# stimulation.net
KiCad netlist of a schematic drawn in EAGLE
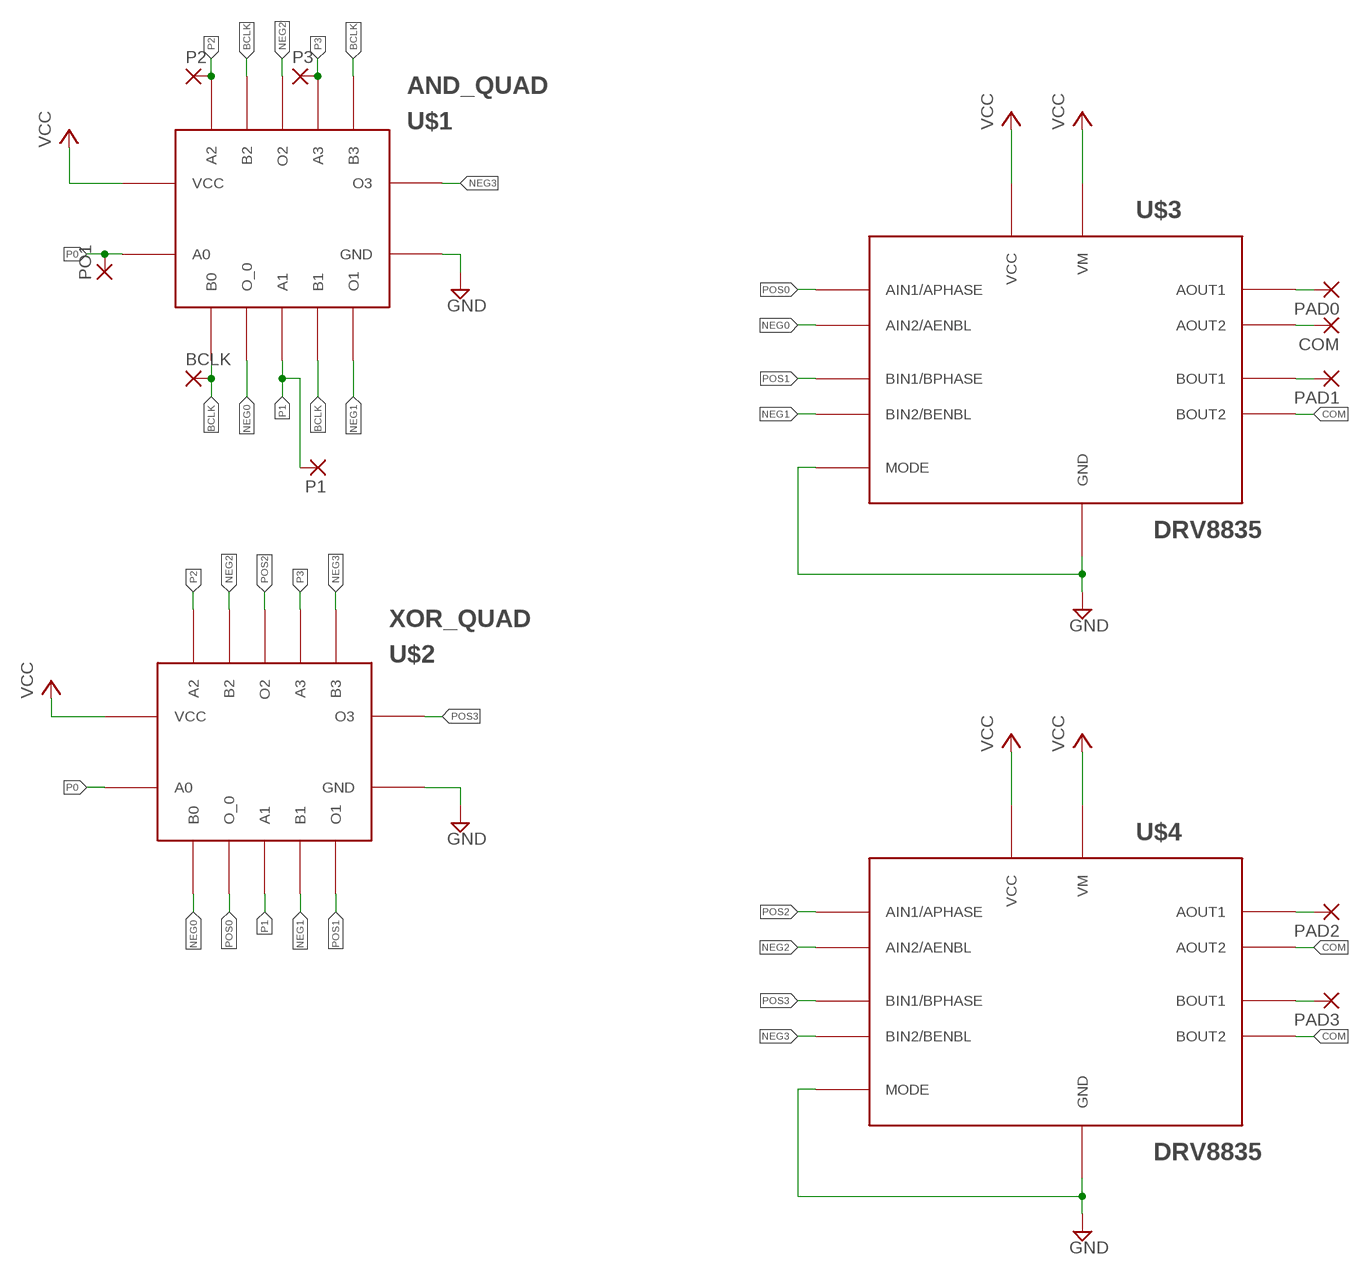
[diagram p0: schematic, sheet 1]

(export (version "E")
  (design (tool "Eeschema 10.0.6"))
  (components
    (comp (ref "BCLK")
      (value "SMD2")
      (footprint "eagle-import:SMD1,27-2,54")
      (libsource (lib "eagle-import") (part "SMD2"))
    )
    (comp (ref "COM")
      (value "SMD2")
      (footprint "eagle-import:SMD1,27-2,54")
      (libsource (lib "eagle-import") (part "SMD2"))
    )
    (comp (ref "P1")
      (value "SMD2")
      (footprint "eagle-import:SMD1,27-2,54")
      (libsource (lib "eagle-import") (part "SMD2"))
    )
    (comp (ref "P2")
      (value "SMD2")
      (footprint "eagle-import:SMD1,27-2,54")
      (libsource (lib "eagle-import") (part "SMD2"))
    )
    (comp (ref "P3")
      (value "SMD2")
      (footprint "eagle-import:SMD1,27-2,54")
      (libsource (lib "eagle-import") (part "SMD2"))
    )
    (comp (ref "PAD0")
      (value "SMD2")
      (footprint "eagle-import:SMD1,27-2,54")
      (libsource (lib "eagle-import") (part "SMD2"))
    )
    (comp (ref "PAD1")
      (value "SMD2")
      (footprint "eagle-import:SMD1,27-2,54")
      (libsource (lib "eagle-import") (part "SMD2"))
    )
    (comp (ref "PAD2")
      (value "SMD2")
      (footprint "eagle-import:SMD1,27-2,54")
      (libsource (lib "eagle-import") (part "SMD2"))
    )
    (comp (ref "PAD3")
      (value "SMD2")
      (footprint "eagle-import:SMD1,27-2,54")
      (libsource (lib "eagle-import") (part "SMD2"))
    )
    (comp (ref "PO1")
      (value "SMD2")
      (footprint "eagle-import:SMD1,27-2,54")
      (libsource (lib "eagle-import") (part "SMD2"))
    )
    (comp (ref "U$1")
      (value "AND_QUAD")
      (footprint "eagle-import:QFN-14")
      (libsource (lib "eagle-import") (part "AND_QUAD"))
    )
    (comp (ref "U$2")
      (value "XOR_QUAD")
      (footprint "eagle-import:QFN-14")
      (libsource (lib "eagle-import") (part "XOR_QUAD"))
    )
    (comp (ref "U$3")
      (value "DRV8835")
      (footprint "eagle-import:QFN-12-HEATSINK")
      (libsource (lib "eagle-import") (part "DRV8835"))
    )
    (comp (ref "U$4")
      (value "DRV8835")
      (footprint "eagle-import:QFN-12-HEATSINK")
      (libsource (lib "eagle-import") (part "DRV8835"))
    )
  )
  (nets
    (net (code "1") (name "BCLK") (class "Default")
      (node (ref "BCLK") (pin "1") (pinfunction "P_1") (pintype "passive"))
      (node (ref "U$1") (pin "B0") (pinfunction "B0_B0") (pintype "input"))
      (node (ref "U$1") (pin "B1") (pinfunction "B1_B1") (pintype "input"))
      (node (ref "U$1") (pin "B2") (pinfunction "B2_B2") (pintype "input"))
      (node (ref "U$1") (pin "B3") (pinfunction "B3_B3") (pintype "input"))
    )
    (net (code "2") (name "COM") (class "Default")
      (node (ref "COM") (pin "1") (pinfunction "P_1") (pintype "passive"))
      (node (ref "U$3") (pin "AOUT2") (pinfunction "AOUT2_AOUT2") (pintype "bidirectional"))
      (node (ref "U$3") (pin "BOUT2") (pinfunction "BOUT2_BOUT2") (pintype "bidirectional"))
      (node (ref "U$4") (pin "AOUT2") (pinfunction "AOUT2_AOUT2") (pintype "bidirectional"))
      (node (ref "U$4") (pin "BOUT2") (pinfunction "BOUT2_BOUT2") (pintype "bidirectional"))
    )
    (net (code "3") (name "GND") (class "Default")
      (node (ref "U$1") (pin "GND") (pinfunction "GND_GND") (pintype "power_in"))
      (node (ref "U$2") (pin "GND") (pinfunction "GND_GND") (pintype "power_in"))
      (node (ref "U$3") (pin "GND") (pinfunction "GND_GND") (pintype "bidirectional"))
      (node (ref "U$3") (pin "MODE") (pinfunction "MODE_MODE") (pintype "bidirectional"))
      (node (ref "U$4") (pin "GND") (pinfunction "GND_GND") (pintype "bidirectional"))
      (node (ref "U$4") (pin "MODE") (pinfunction "MODE_MODE") (pintype "bidirectional"))
    )
    (net (code "4") (name "NEG0") (class "Default")
      (node (ref "U$1") (pin "O_0") (pinfunction "O_0_O_0") (pintype "output"))
      (node (ref "U$2") (pin "B0") (pinfunction "B0_B0") (pintype "input"))
      (node (ref "U$3") (pin "AIN2.AENBL") (pinfunction "AIN2/AENBL_AIN2.AENBL") (pintype "bidirectional"))
    )
    (net (code "5") (name "NEG1") (class "Default")
      (node (ref "U$1") (pin "O1") (pinfunction "O1_O1") (pintype "output"))
      (node (ref "U$2") (pin "B1") (pinfunction "B1_B1") (pintype "input"))
      (node (ref "U$3") (pin "BIN2/BENBL") (pinfunction "BIN2/BENBL_BIN2/BENBL") (pintype "bidirectional"))
    )
    (net (code "6") (name "NEG2") (class "Default")
      (node (ref "U$1") (pin "O2") (pinfunction "O2_O2") (pintype "output"))
      (node (ref "U$2") (pin "B2") (pinfunction "B2_B2") (pintype "input"))
      (node (ref "U$4") (pin "AIN2.AENBL") (pinfunction "AIN2/AENBL_AIN2.AENBL") (pintype "bidirectional"))
    )
    (net (code "7") (name "NEG3") (class "Default")
      (node (ref "U$1") (pin "O3") (pinfunction "O3_O3") (pintype "output"))
      (node (ref "U$2") (pin "B3") (pinfunction "B3_B3") (pintype "input"))
      (node (ref "U$4") (pin "BIN2/BENBL") (pinfunction "BIN2/BENBL_BIN2/BENBL") (pintype "bidirectional"))
    )
    (net (code "8") (name "Net-(P1-P)") (class "Default")
      (node (ref "P1") (pin "1") (pinfunction "P_1") (pintype "passive"))
      (node (ref "U$1") (pin "A1") (pinfunction "A1_A1") (pintype "input"))
    )
    (net (code "9") (name "Net-(P2-P)") (class "Default")
      (node (ref "P2") (pin "1") (pinfunction "P_1") (pintype "passive"))
      (node (ref "U$1") (pin "A2") (pinfunction "A2_A2") (pintype "input"))
    )
    (net (code "10") (name "Net-(P3-P)") (class "Default")
      (node (ref "P3") (pin "1") (pinfunction "P_1") (pintype "passive"))
      (node (ref "U$1") (pin "A3") (pinfunction "A3_A3") (pintype "input"))
    )
    (net (code "11") (name "Net-(PAD0-P)") (class "Default")
      (node (ref "PAD0") (pin "1") (pinfunction "P_1") (pintype "passive"))
      (node (ref "U$3") (pin "AOUT1") (pinfunction "AOUT1_AOUT1") (pintype "bidirectional"))
    )
    (net (code "12") (name "Net-(PAD1-P)") (class "Default")
      (node (ref "PAD1") (pin "1") (pinfunction "P_1") (pintype "passive"))
      (node (ref "U$3") (pin "BOUT1") (pinfunction "BOUT1_BOUT1") (pintype "bidirectional"))
    )
    (net (code "13") (name "Net-(PAD2-P)") (class "Default")
      (node (ref "PAD2") (pin "1") (pinfunction "P_1") (pintype "passive"))
      (node (ref "U$4") (pin "AOUT1") (pinfunction "AOUT1_AOUT1") (pintype "bidirectional"))
    )
    (net (code "14") (name "Net-(PAD3-P)") (class "Default")
      (node (ref "PAD3") (pin "1") (pinfunction "P_1") (pintype "passive"))
      (node (ref "U$4") (pin "BOUT1") (pinfunction "BOUT1_BOUT1") (pintype "bidirectional"))
    )
    (net (code "15") (name "Net-(PO1-P)") (class "Default")
      (node (ref "PO1") (pin "1") (pinfunction "P_1") (pintype "passive"))
      (node (ref "U$1") (pin "A0") (pinfunction "A0_A0") (pintype "input"))
    )
    (net (code "16") (name "P0") (class "Default")
      (node (ref "U$2") (pin "A0") (pinfunction "A0_A0") (pintype "input"))
    )
    (net (code "17") (name "P1") (class "Default")
      (node (ref "U$2") (pin "A1") (pinfunction "A1_A1") (pintype "input"))
    )
    (net (code "18") (name "P2") (class "Default")
      (node (ref "U$2") (pin "A2") (pinfunction "A2_A2") (pintype "input"))
    )
    (net (code "19") (name "P3") (class "Default")
      (node (ref "U$2") (pin "A3") (pinfunction "A3_A3") (pintype "input"))
    )
    (net (code "20") (name "POS0") (class "Default")
      (node (ref "U$2") (pin "O_0") (pinfunction "O_0_O_0") (pintype "output"))
      (node (ref "U$3") (pin "AIN1/APHASE") (pinfunction "AIN1/APHASE_AIN1/APHASE") (pintype "bidirectional"))
    )
    (net (code "21") (name "POS1") (class "Default")
      (node (ref "U$2") (pin "O1") (pinfunction "O1_O1") (pintype "output"))
      (node (ref "U$3") (pin "BIN1/BPHASE") (pinfunction "BIN1/BPHASE_BIN1/BPHASE") (pintype "bidirectional"))
    )
    (net (code "22") (name "POS2") (class "Default")
      (node (ref "U$2") (pin "O2") (pinfunction "O2_O2") (pintype "output"))
      (node (ref "U$4") (pin "AIN1/APHASE") (pinfunction "AIN1/APHASE_AIN1/APHASE") (pintype "bidirectional"))
    )
    (net (code "23") (name "POS3") (class "Default")
      (node (ref "U$2") (pin "O3") (pinfunction "O3_O3") (pintype "output"))
      (node (ref "U$4") (pin "BIN1/BPHASE") (pinfunction "BIN1/BPHASE_BIN1/BPHASE") (pintype "bidirectional"))
    )
    (net (code "24") (name "VCC") (class "Default")
      (node (ref "U$1") (pin "VCC") (pinfunction "VCC_VCC") (pintype "power_in"))
      (node (ref "U$2") (pin "VCC") (pinfunction "VCC_VCC") (pintype "power_in"))
      (node (ref "U$3") (pin "VCC") (pinfunction "VCC_VCC") (pintype "bidirectional"))
      (node (ref "U$3") (pin "VM") (pinfunction "VM_VM") (pintype "bidirectional"))
      (node (ref "U$4") (pin "VCC") (pinfunction "VCC_VCC") (pintype "bidirectional"))
      (node (ref "U$4") (pin "VM") (pinfunction "VM_VM") (pintype "bidirectional"))
    )
  )
)
